# ESP32_C5.net
KiCad netlist of a schematic drawn in Altium Designer
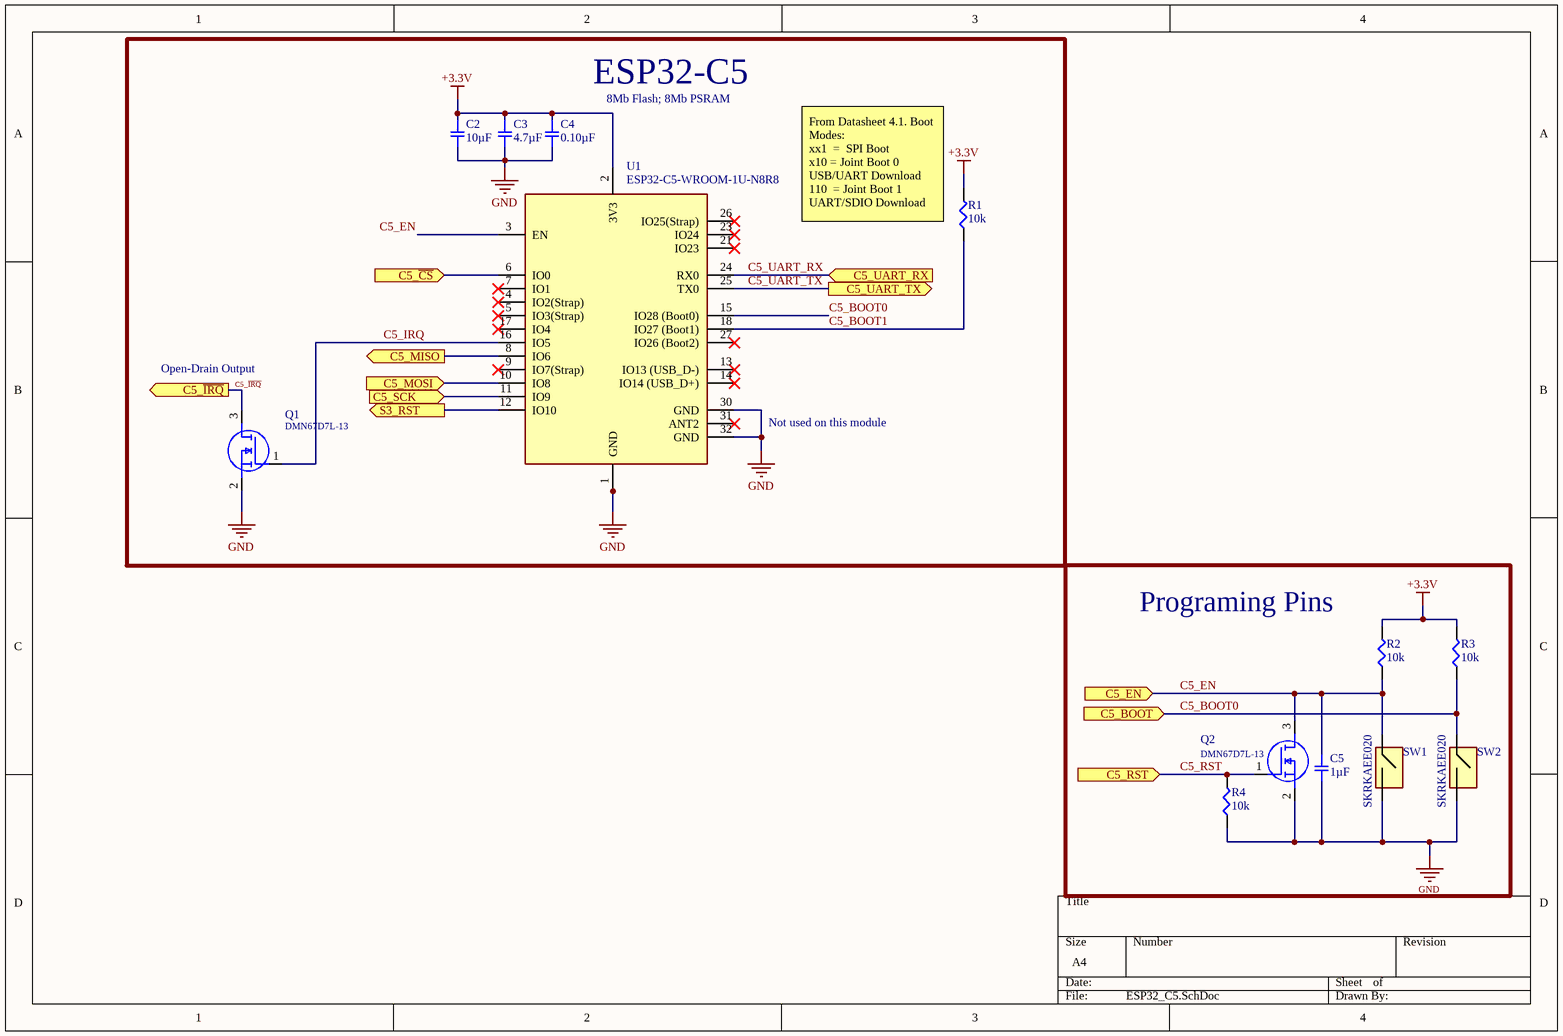
[diagram p0: ESP32_C5.SchDoc]

(export (version "E")
  (design (tool "Eeschema 10.0.6"))
  (components
    (comp (ref "C2")
      (value "10µF")
      (footprint "SMD-0603C")
      (description "CAP CER 10UF 6.3V X5R 0603")
      (fields
        (field (name "DIGI-KEY PART NUMBER") "490-10467-1-ND")
        (field (name "PART NUMBER") "GRM185R60J106ME15D")
      )
      (libsource (lib "capacitor_murata_0603") (part "GRM185R60J106ME15D"))
    )
    (comp (ref "C3")
      (value "4.7µF")
      (footprint "SMD-0402C")
      (description "CAP CER 4.7UF 6.3V X5R 0402")
      (fields
        (field (name "DIGI-KEY PART NUMBER") "490-13232-1-ND")
        (field (name "PART NUMBER") "GRM153R60J475ME15D")
      )
      (libsource (lib "capacitor_murata_0402") (part "GRM153R60J475ME15D"))
    )
    (comp (ref "C4")
      (value "0.10µF")
      (footprint "SMD-0402C")
      (description "CAP CER 0.1UF 16V X7R 0402")
      (fields
        (field (name "DIGI-KEY PART NUMBER") "490-4759-1-ND")
        (field (name "PART NUMBER") "GCM155R71C104KA55D")
      )
      (libsource (lib "capacitor_murata_0402") (part "GCM155R71C104KA55D"))
    )
    (comp (ref "C5")
      (value "1µF")
      (footprint "SMD-0402C")
      (description "CAP CER 1UF 10V X7S 0402")
      (fields
        (field (name "DIGI-KEY PART NUMBER") "490-13409-1-ND")
        (field (name "PART NUMBER") "GCM155C71A105KE38D")
      )
      (libsource (lib "capacitor_murata_0402") (part "GCM155C71A105KE38D"))
    )
    (comp (ref "Q1")
      (value "DMN67D7L-13")
      (footprint "SamacSys:DMN67D7L13")
      (description "MOSFET (N-Channel)")
      (fields (field (name "MOUSER PART NUMBER") "621-DMN67D7L-13"))
      (libsource (lib "*") (part "DMN67D7L-13"))
    )
    (comp (ref "Q2")
      (value "DMN67D7L-13")
      (footprint "SamacSys:DMN67D7L13")
      (description "MOSFET (N-Channel)")
      (fields (field (name "MOUSER PART NUMBER") "621-DMN67D7L-13"))
      (libsource (lib "*") (part "DMN67D7L-13"))
    )
    (comp (ref "R1")
      (value "10k")
      (footprint "SMD-0402-RES")
      (description "RES SMD 10K OHM 1% 1/10W 0402")
      (fields
        (field (name "PART NUMBER") "ERJ-2RKF1002X")
        (field (name "DIGI-KEY PART NUMBER") "P10.0KLCT-ND")
      )
      (libsource (lib "Panasonic_ERJ_0402") (part "ERJ-2RKF1002X"))
    )
    (comp (ref "R2")
      (value "10k")
      (footprint "SMD-0402-RES")
      (description "RES SMD 10K OHM 1% 1/10W 0402")
      (fields
        (field (name "PART NUMBER") "ERJ-2RKF1002X")
        (field (name "DIGI-KEY PART NUMBER") "P10.0KLCT-ND")
      )
      (libsource (lib "Panasonic_ERJ_0402") (part "ERJ-2RKF1002X"))
    )
    (comp (ref "R3")
      (value "10k")
      (footprint "SMD-0402-RES")
      (description "RES SMD 10K OHM 1% 1/10W 0402")
      (fields
        (field (name "PART NUMBER") "ERJ-2RKF1002X")
        (field (name "DIGI-KEY PART NUMBER") "P10.0KLCT-ND")
      )
      (libsource (lib "Panasonic_ERJ_0402") (part "ERJ-2RKF1002X"))
    )
    (comp (ref "R4")
      (value "10k")
      (footprint "SMD-0402-RES")
      (description "RES SMD 10K OHM 1% 1/10W 0402")
      (fields
        (field (name "PART NUMBER") "ERJ-2RKF1002X")
        (field (name "DIGI-KEY PART NUMBER") "P10.0KLCT-ND")
      )
      (libsource (lib "Panasonic_ERJ_0402") (part "ERJ-2RKF1002X"))
    )
    (comp (ref "SW1")
      (value "SKRKAEE020")
      (footprint "SKRKAEE020")
      (description "Tactile Switches 3.9x2.9x2.0mm 160gf Packaging Temp 80oC")
      (fields (field (name "MOUSER PART NUMBER") "688-SKRKAEE020"))
      (libsource (lib "SomoPowerPackControl") (part "SKRKAEE020"))
    )
    (comp (ref "SW2")
      (value "SKRKAEE020")
      (footprint "SKRKAEE020")
      (description "Tactile Switches 3.9x2.9x2.0mm 160gf Packaging Temp 80oC")
      (fields (field (name "MOUSER PART NUMBER") "688-SKRKAEE020"))
      (libsource (lib "SomoPowerPackControl") (part "SKRKAEE020"))
    )
    (comp (ref "U1")
      (value "ESP32-C5-WROOM-1U-N8R8")
      (footprint "ESP32C5WROOM1UN8R8")
      (description "Integrated Circuit")
      (fields (field (name "MANUFACTURER_PART_NUMBER") "ESP32-C5-WROOM-1-N8R8"))
      (libsource (lib "SomoPowerPackControl") (part "ESP32-C5-WROOM-1U-N8R8"))
    )
  )
  (nets
    (net (code "1") (name "+3.3V") (class "Default")
      (node (ref "C2") (pin "1") (pinfunction "1_1") (pintype "passive"))
      (node (ref "C3") (pin "1") (pinfunction "1_1") (pintype "passive"))
      (node (ref "C4") (pin "1") (pinfunction "1_1") (pintype "passive"))
      (node (ref "R1") (pin "2") (pinfunction "2_2") (pintype "passive"))
      (node (ref "R2") (pin "2") (pinfunction "2_2") (pintype "passive"))
      (node (ref "R3") (pin "2") (pinfunction "2_2") (pintype "passive"))
      (node (ref "U1") (pin "2") (pinfunction "3V3_2") (pintype "passive"))
    )
    (net (code "2") (name "/C5_BOOT0") (class "Default")
      (node (ref "R3") (pin "1") (pinfunction "1_1") (pintype "passive"))
      (node (ref "SW2") (pin "1") (pinfunction "1_1") (pintype "passive"))
      (node (ref "U1") (pin "15") (pinfunction "IO28_(Boot0)_15") (pintype "passive"))
    )
    (net (code "3") (name "/C5_BOOT1") (class "Default")
      (node (ref "R1") (pin "1") (pinfunction "1_1") (pintype "passive"))
      (node (ref "U1") (pin "18") (pinfunction "IO27_(Boot1)_18") (pintype "passive"))
    )
    (net (code "4") (name "/C5_EN") (class "Default")
      (node (ref "C5") (pin "1") (pinfunction "1_1") (pintype "passive"))
      (node (ref "Q2") (pin "3") (pinfunction "D_3") (pintype "passive"))
      (node (ref "R2") (pin "1") (pinfunction "1_1") (pintype "passive"))
      (node (ref "SW1") (pin "1") (pinfunction "1_1") (pintype "passive"))
      (node (ref "U1") (pin "3") (pinfunction "EN_3") (pintype "passive"))
    )
    (net (code "5") (name "/C5_IRQ") (class "Default")
      (node (ref "Q1") (pin "1") (pinfunction "G_1") (pintype "passive"))
      (node (ref "U1") (pin "16") (pinfunction "IO5_16") (pintype "passive"))
    )
    (net (code "6") (name "/C5_MISO") (class "Default")
      (node (ref "U1") (pin "8") (pinfunction "IO6_8") (pintype "passive"))
    )
    (net (code "7") (name "/C5_MOSI") (class "Default")
      (node (ref "U1") (pin "10") (pinfunction "IO8_10") (pintype "passive"))
    )
    (net (code "8") (name "/C5_RST") (class "Default")
      (node (ref "Q2") (pin "1") (pinfunction "G_1") (pintype "passive"))
      (node (ref "R4") (pin "2") (pinfunction "2_2") (pintype "passive"))
    )
    (net (code "9") (name "/C5_SCK") (class "Default")
      (node (ref "U1") (pin "11") (pinfunction "IO9_11") (pintype "passive"))
    )
    (net (code "10") (name "/C5_UART_RX") (class "Default")
      (node (ref "U1") (pin "24") (pinfunction "RX0_24") (pintype "passive"))
    )
    (net (code "11") (name "/C5_UART_TX") (class "Default")
      (node (ref "U1") (pin "25") (pinfunction "TX0_25") (pintype "passive"))
    )
    (net (code "12") (name "/C5_~{CS}") (class "Default")
      (node (ref "U1") (pin "6") (pinfunction "IO0_6") (pintype "passive"))
    )
    (net (code "13") (name "/C5_~{IRQ}") (class "Default")
      (node (ref "Q1") (pin "3") (pinfunction "D_3") (pintype "passive"))
    )
    (net (code "14") (name "/S3_RST") (class "Default")
      (node (ref "U1") (pin "12") (pinfunction "IO10_12") (pintype "passive"))
    )
    (net (code "15") (name "GND") (class "Default")
      (node (ref "C2") (pin "2") (pinfunction "2_2") (pintype "passive"))
      (node (ref "C3") (pin "2") (pinfunction "2_2") (pintype "passive"))
      (node (ref "C4") (pin "2") (pinfunction "2_2") (pintype "passive"))
      (node (ref "C5") (pin "2") (pinfunction "2_2") (pintype "passive"))
      (node (ref "Q1") (pin "2") (pinfunction "S_2") (pintype "passive"))
      (node (ref "Q2") (pin "2") (pinfunction "S_2") (pintype "passive"))
      (node (ref "R4") (pin "1") (pinfunction "1_1") (pintype "passive"))
      (node (ref "SW1") (pin "2") (pinfunction "2_2") (pintype "passive"))
      (node (ref "SW2") (pin "2") (pinfunction "2_2") (pintype "passive"))
      (node (ref "U1") (pin "1") (pinfunction "GND_1") (pintype "passive"))
      (node (ref "U1") (pin "28") (pinfunction "GND_28") (pintype "passive"))
      (node (ref "U1") (pin "29") (pinfunction "GND_29") (pintype "passive"))
      (node (ref "U1") (pin "30") (pinfunction "GND_30") (pintype "passive"))
      (node (ref "U1") (pin "32") (pinfunction "GND_32") (pintype "passive"))
    )
    (net (code "16") (name "unconnected-(U1-ANT2-Pad31)") (class "Default")
      (node (ref "U1") (pin "31") (pinfunction "ANT2_31") (pintype "passive+no_connect"))
    )
    (net (code "17") (name "unconnected-(U1-IO1-Pad7)") (class "Default")
      (node (ref "U1") (pin "7") (pinfunction "IO1_7") (pintype "passive+no_connect"))
    )
    (net (code "18") (name "unconnected-(U1-IO2(Strap)-Pad4)") (class "Default")
      (node (ref "U1") (pin "4") (pinfunction "IO2(Strap)_4") (pintype "passive+no_connect"))
    )
    (net (code "19") (name "unconnected-(U1-IO3(Strap)-Pad5)") (class "Default")
      (node (ref "U1") (pin "5") (pinfunction "IO3(Strap)_5") (pintype "passive+no_connect"))
    )
    (net (code "20") (name "unconnected-(U1-IO4-Pad17)") (class "Default")
      (node (ref "U1") (pin "17") (pinfunction "IO4_17") (pintype "passive+no_connect"))
    )
    (net (code "21") (name "unconnected-(U1-IO7(Strap)-Pad9)") (class "Default")
      (node (ref "U1") (pin "9") (pinfunction "IO7(Strap)_9") (pintype "passive+no_connect"))
    )
    (net (code "22") (name "unconnected-(U1-IO13_(USB_D-)-Pad13)") (class "Default")
      (node (ref "U1") (pin "13") (pinfunction "IO13_(USB_D-)_13") (pintype "passive+no_connect"))
    )
    (net (code "23") (name "unconnected-(U1-IO14_(USB_D+)-Pad14)") (class "Default")
      (node (ref "U1") (pin "14") (pinfunction "IO14_(USB_D+)_14") (pintype "passive+no_connect"))
    )
    (net (code "24") (name "unconnected-(U1-IO23-Pad21)") (class "Default")
      (node (ref "U1") (pin "21") (pinfunction "IO23_21") (pintype "passive+no_connect"))
    )
    (net (code "25") (name "unconnected-(U1-IO24-Pad23)") (class "Default")
      (node (ref "U1") (pin "22") (pinfunction "NC_2_22") (pintype "passive"))
      (node (ref "U1") (pin "23") (pinfunction "IO24_23") (pintype "passive"))
    )
    (net (code "26") (name "unconnected-(U1-IO25(Strap)-Pad26)") (class "Default")
      (node (ref "U1") (pin "26") (pinfunction "IO25(Strap)_26") (pintype "passive+no_connect"))
    )
    (net (code "27") (name "unconnected-(U1-IO26_(Boot2)-Pad27)") (class "Default")
      (node (ref "U1") (pin "27") (pinfunction "IO26_(Boot2)_27") (pintype "passive+no_connect"))
    )
    (net (code "28") (name "unconnected-(U1-NC_1-Pad20)") (class "Default")
      (node (ref "U1") (pin "20") (pinfunction "NC_1_20") (pintype "passive"))
    )
    (net (code "29") (name "unconnected-(U1-NC{slash}IO15-Pad19)") (class "Default")
      (node (ref "U1") (pin "19") (pinfunction "NC/IO15_19") (pintype "passive"))
    )
  )
)
